# MainController.net
KiCad netlist of a schematic drawn in EAGLE
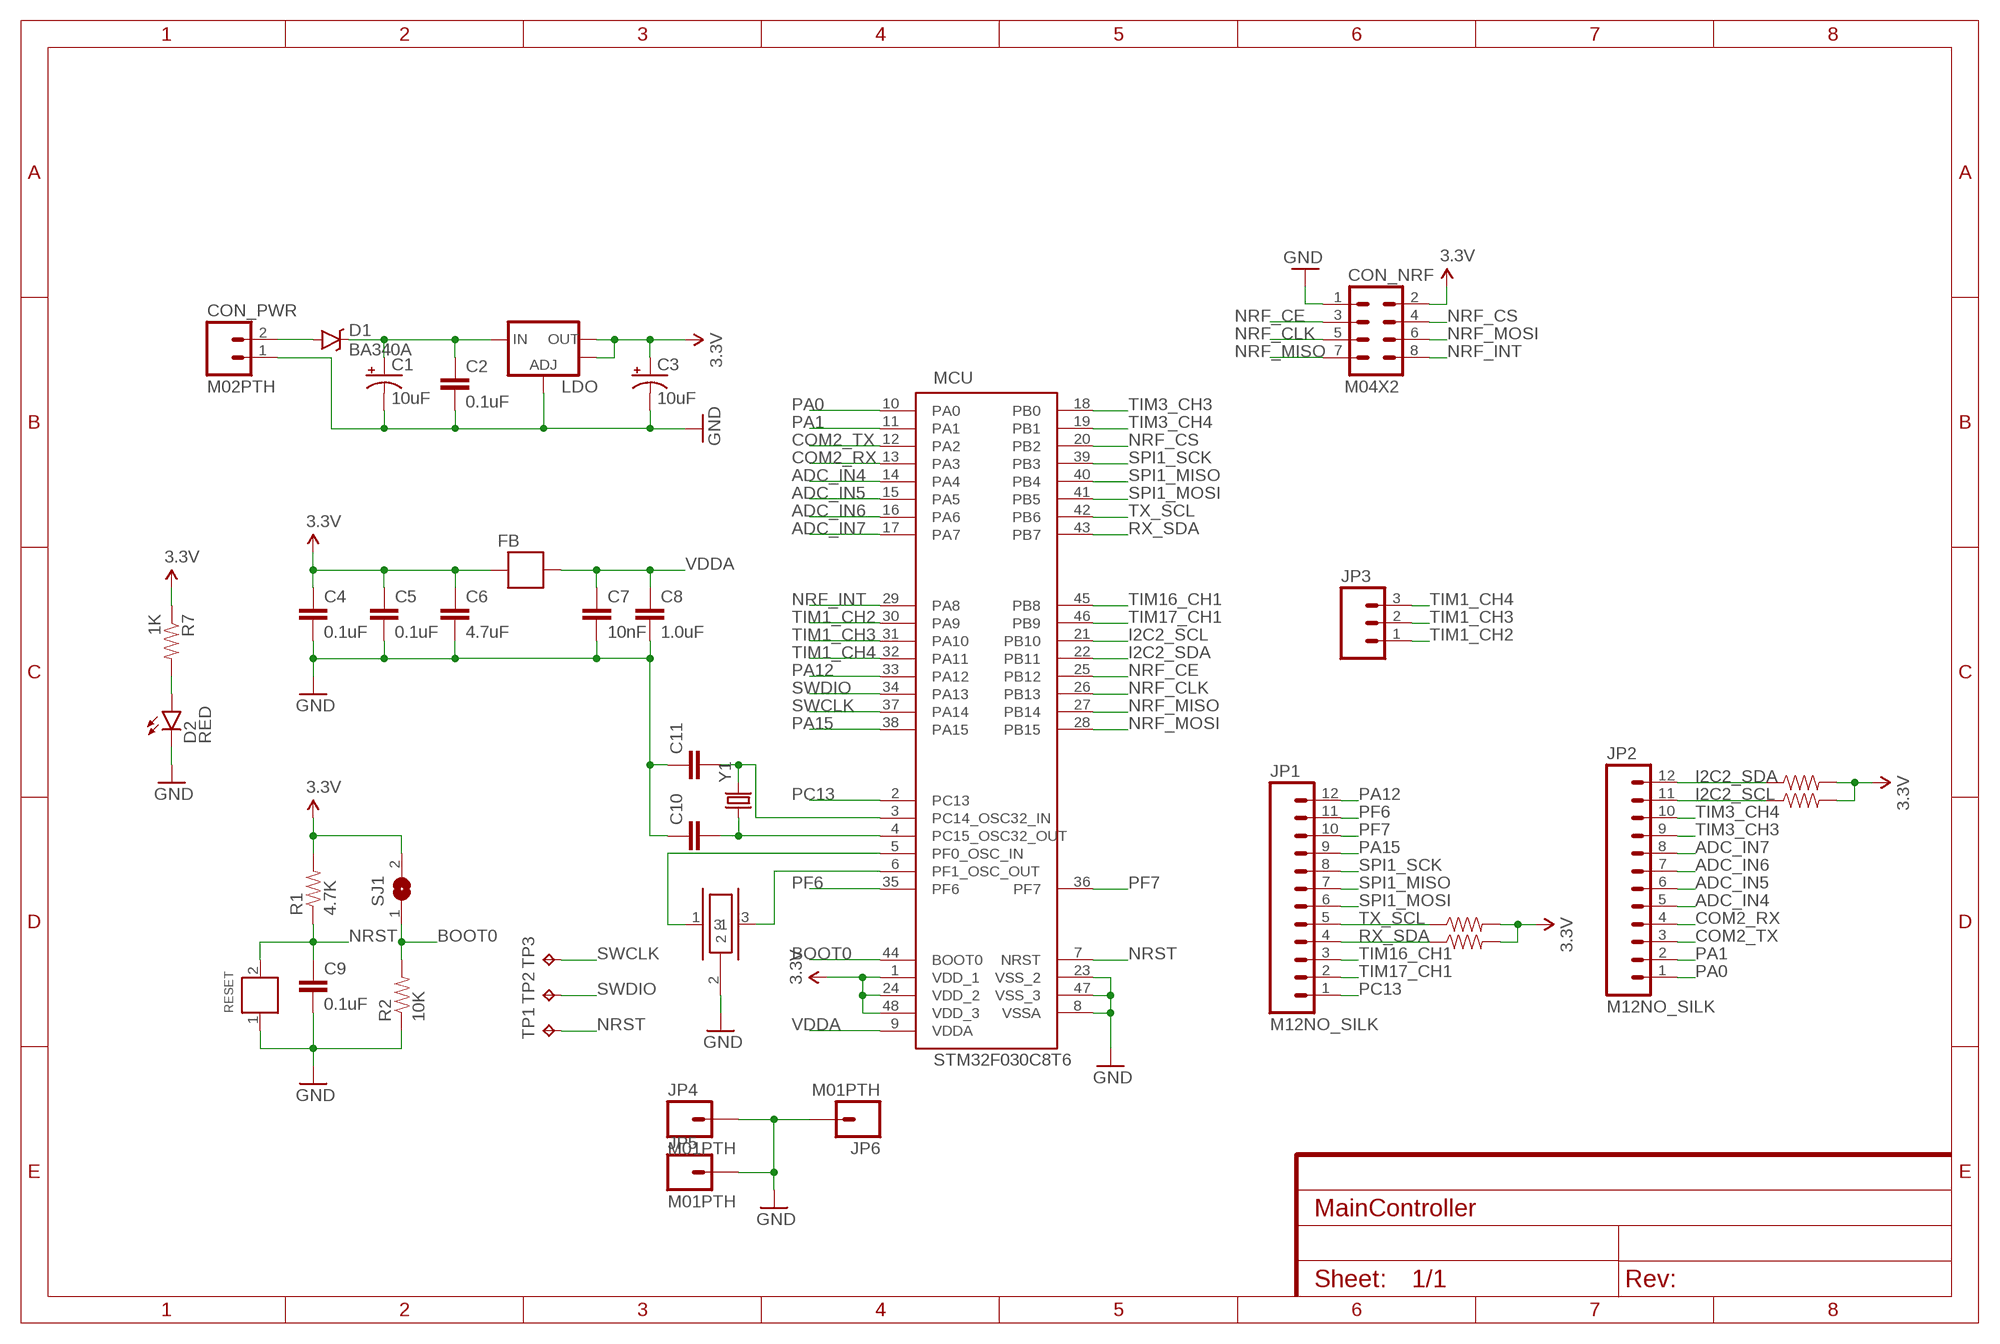
[diagram p0: schematic, sheet 1]

(export (version "E")
  (design (tool "Eeschema 10.0.6"))
  (components
    (comp (ref "C1")
      (value "10uF")
      (footprint "eagle-import:EIA3216")
      (libsource (lib "eagle-import") (part "10UF-16V-10%(TANT)"))
    )
    (comp (ref "C2")
      (value "0.1uF")
      (footprint "eagle-import:0603-CAP")
      (libsource (lib "eagle-import") (part "0.1UF-25V-5%(0603)"))
    )
    (comp (ref "C3")
      (value "10uF")
      (footprint "eagle-import:EIA3216")
      (libsource (lib "eagle-import") (part "10UF-16V-10%(TANT)"))
    )
    (comp (ref "C4")
      (value "0.1uF")
      (footprint "eagle-import:0603-CAP")
      (libsource (lib "eagle-import") (part "0.1UF-25V-5%(0603)"))
    )
    (comp (ref "C5")
      (value "0.1uF")
      (footprint "eagle-import:0603-CAP")
      (libsource (lib "eagle-import") (part "0.1UF-25V-5%(0603)"))
    )
    (comp (ref "C6")
      (value "4.7uF")
      (footprint "eagle-import:0603-CAP")
      (libsource (lib "eagle-import") (part "4.7UF-6.3V-10%(0603)0603"))
    )
    (comp (ref "C7")
      (value "10nF")
      (footprint "eagle-import:0603-CAP")
      (libsource (lib "eagle-import") (part "10NF/10000PF-50V-10%(0603)"))
    )
    (comp (ref "C8")
      (value "1.0uF")
      (footprint "eagle-import:0603-CAP")
      (libsource (lib "eagle-import") (part "1.0UF-16V-10%(0603)"))
    )
    (comp (ref "C9")
      (value "0.1uF")
      (footprint "eagle-import:0603-CAP")
      (libsource (lib "eagle-import") (part "0.1UF-100V-10%(0603)"))
    )
    (comp (ref "C10")
      (value "CAP0603-CAP")
      (footprint "eagle-import:0603-CAP")
      (libsource (lib "eagle-import") (part "CAP0603-CAP"))
    )
    (comp (ref "C11")
      (value "CAP0603-CAP")
      (footprint "eagle-import:0603-CAP")
      (libsource (lib "eagle-import") (part "CAP0603-CAP"))
    )
    (comp (ref "CON_NRF")
      (value "M04X2")
      (footprint "eagle-import:2X4")
      (libsource (lib "eagle-import") (part "M04X2"))
    )
    (comp (ref "CON_PWR")
      (value "M02PTH")
      (footprint "eagle-import:1X02")
      (libsource (lib "eagle-import") (part "M02PTH"))
    )
    (comp (ref "D1")
      (value "BA340A")
      (footprint "eagle-import:SMA-DIODE")
      (libsource (lib "eagle-import") (part "B340A"))
    )
    (comp (ref "D2")
      (value "RED")
      (footprint "eagle-import:LED-0603")
      (libsource (lib "eagle-import") (part "LED-RED0603"))
    )
    (comp (ref "FB")
      (value "FBFB0805")
      (footprint "eagle-import:0805W")
      (libsource (lib "eagle-import") (part "FBFB0805"))
    )
    (comp (ref "JP1")
      (value "M12NO_SILK")
      (footprint "eagle-import:1X12_NO_SILK")
      (libsource (lib "eagle-import") (part "M12NO_SILK"))
    )
    (comp (ref "JP2")
      (value "M12NO_SILK")
      (footprint "eagle-import:1X12_NO_SILK")
      (libsource (lib "eagle-import") (part "M12NO_SILK"))
    )
    (comp (ref "JP3")
      (value "M031X03_NO_SILK")
      (footprint "eagle-import:1X03_NO_SILK")
      (libsource (lib "eagle-import") (part "M031X03_NO_SILK"))
    )
    (comp (ref "JP4")
      (value "M01PTH")
      (footprint "eagle-import:1X01")
      (libsource (lib "eagle-import") (part "M01PTH"))
    )
    (comp (ref "JP5")
      (value "M01PTH")
      (footprint "eagle-import:1X01")
      (libsource (lib "eagle-import") (part "M01PTH"))
    )
    (comp (ref "JP6")
      (value "M01PTH")
      (footprint "eagle-import:1X01")
      (libsource (lib "eagle-import") (part "M01PTH"))
    )
    (comp (ref "LDO")
      (value "V_REG_LM1117SOT223")
      (footprint "eagle-import:SOT223")
      (libsource (lib "eagle-import") (part "V_REG_LM1117SOT223"))
    )
    (comp (ref "MCU")
      (value "STM32F030C8T6")
      (footprint "eagle-import:TQFP48")
      (libsource (lib "eagle-import") (part "STM32F030C8T6"))
    )
    (comp (ref "OSC")
      (value "CSTCE8M00G52-R0")
      (footprint "eagle-import:CSTCE_M_G")
      (libsource (lib "eagle-import") (part "CSTCE8M00G52-R0"))
    )
    (comp (ref "R1")
      (value "4.7K")
      (footprint "eagle-import:0603-RES")
      (libsource (lib "eagle-import") (part "4.7KOHM-1/10W-1%(0603)"))
    )
    (comp (ref "R2")
      (value "10K")
      (footprint "eagle-import:0603-RES")
      (libsource (lib "eagle-import") (part "10KOHM-1/10W-1%(0603)0603"))
    )
    (comp (ref "R3")
      (value "10K")
      (footprint "eagle-import:0603-RES")
      (libsource (lib "eagle-import") (part "10OHM-1/10W-5%0603SMD"))
    )
    (comp (ref "R4")
      (value "10K")
      (footprint "eagle-import:0603-RES")
      (libsource (lib "eagle-import") (part "10OHM-1/10W-5%0603SMD"))
    )
    (comp (ref "R5")
      (value "10K")
      (footprint "eagle-import:0603-RES")
      (libsource (lib "eagle-import") (part "10OHM-1/10W-5%0603SMD"))
    )
    (comp (ref "R6")
      (value "10K")
      (footprint "eagle-import:0603-RES")
      (libsource (lib "eagle-import") (part "10OHM-1/10W-5%0603SMD"))
    )
    (comp (ref "R7")
      (value "1K")
      (footprint "eagle-import:0603-RES")
      (libsource (lib "eagle-import") (part "1KOHM-1/10W-1%(0603)"))
    )
    (comp (ref "RESET")
      (value "SWITCH_SMD")
      (footprint "eagle-import:SWITCH3X6_SMD")
      (libsource (lib "eagle-import") (part "SWITCH_SMD"))
    )
    (comp (ref "SJ1") (value "SJ") (footprint "eagle-import:SJ") (libsource (lib "eagle-import") (part "SJ")))
    (comp (ref "TP1")
      (value "TPB1,27")
      (footprint "eagle-import:B1,27")
      (libsource (lib "eagle-import") (part "TPB1,27"))
    )
    (comp (ref "TP2")
      (value "TPB1,27")
      (footprint "eagle-import:B1,27")
      (libsource (lib "eagle-import") (part "TPB1,27"))
    )
    (comp (ref "TP3")
      (value "TPB1,27")
      (footprint "eagle-import:B1,27")
      (libsource (lib "eagle-import") (part "TPB1,27"))
    )
    (comp (ref "Y1")
      (value "CRYSTALTC38H")
      (footprint "eagle-import:TC38H")
      (libsource (lib "eagle-import") (part "CRYSTALTC38H"))
    )
  )
  (nets
    (net (code "1") (name "/ADC_IN4") (class "Default")
      (node (ref "JP2") (pin "5") (pinfunction "5_5") (pintype "passive"))
      (node (ref "MCU") (pin "14") (pinfunction "PA4_14") (pintype "bidirectional"))
    )
    (net (code "2") (name "/ADC_IN5") (class "Default")
      (node (ref "JP2") (pin "6") (pinfunction "6_6") (pintype "passive"))
      (node (ref "MCU") (pin "15") (pinfunction "PA5_15") (pintype "bidirectional"))
    )
    (net (code "3") (name "/ADC_IN6") (class "Default")
      (node (ref "JP2") (pin "7") (pinfunction "7_7") (pintype "passive"))
      (node (ref "MCU") (pin "16") (pinfunction "PA6_16") (pintype "bidirectional"))
    )
    (net (code "4") (name "/ADC_IN7") (class "Default")
      (node (ref "JP2") (pin "8") (pinfunction "8_8") (pintype "passive"))
      (node (ref "MCU") (pin "17") (pinfunction "PA7_17") (pintype "bidirectional"))
    )
    (net (code "5") (name "/BOOT0") (class "Default")
      (node (ref "MCU") (pin "44") (pinfunction "BOOT0_44") (pintype "bidirectional"))
      (node (ref "R2") (pin "2") (pinfunction "2_2") (pintype "passive"))
      (node (ref "SJ1") (pin "1") (pinfunction "1_1") (pintype "passive"))
    )
    (net (code "6") (name "/COM2_RX") (class "Default")
      (node (ref "JP2") (pin "4") (pinfunction "4_4") (pintype "passive"))
      (node (ref "MCU") (pin "13") (pinfunction "PA3_13") (pintype "bidirectional"))
    )
    (net (code "7") (name "/COM2_TX") (class "Default")
      (node (ref "JP2") (pin "3") (pinfunction "3_3") (pintype "passive"))
      (node (ref "MCU") (pin "12") (pinfunction "PA2_12") (pintype "bidirectional"))
    )
    (net (code "8") (name "/I2C2_SCL") (class "Default")
      (node (ref "JP2") (pin "11") (pinfunction "11_11") (pintype "passive"))
      (node (ref "MCU") (pin "21") (pinfunction "PB10_21") (pintype "bidirectional"))
      (node (ref "R5") (pin "1") (pinfunction "1_1") (pintype "passive"))
    )
    (net (code "9") (name "/I2C2_SDA") (class "Default")
      (node (ref "JP2") (pin "12") (pinfunction "12_12") (pintype "passive"))
      (node (ref "MCU") (pin "22") (pinfunction "PB11_22") (pintype "bidirectional"))
      (node (ref "R6") (pin "1") (pinfunction "1_1") (pintype "passive"))
    )
    (net (code "10") (name "/NRF_CE") (class "Default")
      (node (ref "CON_NRF") (pin "3") (pinfunction "3_3") (pintype "passive"))
      (node (ref "MCU") (pin "25") (pinfunction "PB12_25") (pintype "bidirectional"))
    )
    (net (code "11") (name "/NRF_CLK") (class "Default")
      (node (ref "CON_NRF") (pin "5") (pinfunction "5_5") (pintype "passive"))
      (node (ref "MCU") (pin "26") (pinfunction "PB13_26") (pintype "bidirectional"))
    )
    (net (code "12") (name "/NRF_CS") (class "Default")
      (node (ref "CON_NRF") (pin "4") (pinfunction "4_4") (pintype "passive"))
      (node (ref "MCU") (pin "20") (pinfunction "PB2_20") (pintype "bidirectional"))
    )
    (net (code "13") (name "/NRF_INT") (class "Default")
      (node (ref "CON_NRF") (pin "8") (pinfunction "8_8") (pintype "passive"))
      (node (ref "MCU") (pin "29") (pinfunction "PA8_29") (pintype "bidirectional"))
    )
    (net (code "14") (name "/NRF_MISO") (class "Default")
      (node (ref "CON_NRF") (pin "7") (pinfunction "7_7") (pintype "passive"))
      (node (ref "MCU") (pin "27") (pinfunction "PB14_27") (pintype "bidirectional"))
    )
    (net (code "15") (name "/NRF_MOSI") (class "Default")
      (node (ref "CON_NRF") (pin "6") (pinfunction "6_6") (pintype "passive"))
      (node (ref "MCU") (pin "28") (pinfunction "PB15_28") (pintype "bidirectional"))
    )
    (net (code "16") (name "/NRST") (class "Default")
      (node (ref "C9") (pin "1") (pinfunction "1_1") (pintype "passive"))
      (node (ref "MCU") (pin "7") (pinfunction "NRST_7") (pintype "bidirectional"))
      (node (ref "R1") (pin "1") (pinfunction "1_1") (pintype "passive"))
      (node (ref "RESET") (pin "2") (pinfunction "2_2") (pintype "bidirectional"))
      (node (ref "TP1") (pin "TP") (pinfunction "TP_TP") (pintype "input"))
    )
    (net (code "17") (name "/PA0") (class "Default")
      (node (ref "JP2") (pin "1") (pinfunction "1_1") (pintype "passive"))
      (node (ref "MCU") (pin "10") (pinfunction "PA0_10") (pintype "bidirectional"))
    )
    (net (code "18") (name "/PA1") (class "Default")
      (node (ref "JP2") (pin "2") (pinfunction "2_2") (pintype "passive"))
      (node (ref "MCU") (pin "11") (pinfunction "PA1_11") (pintype "bidirectional"))
    )
    (net (code "19") (name "/PA12") (class "Default")
      (node (ref "JP1") (pin "12") (pinfunction "12_12") (pintype "passive"))
      (node (ref "MCU") (pin "33") (pinfunction "PA12_33") (pintype "bidirectional"))
    )
    (net (code "20") (name "/PA15") (class "Default")
      (node (ref "JP1") (pin "9") (pinfunction "9_9") (pintype "passive"))
      (node (ref "MCU") (pin "38") (pinfunction "PA15_38") (pintype "bidirectional"))
    )
    (net (code "21") (name "/PC13") (class "Default")
      (node (ref "JP1") (pin "1") (pinfunction "1_1") (pintype "passive"))
      (node (ref "MCU") (pin "2") (pinfunction "PC13_2") (pintype "bidirectional"))
    )
    (net (code "22") (name "/PF6") (class "Default")
      (node (ref "JP1") (pin "11") (pinfunction "11_11") (pintype "passive"))
      (node (ref "MCU") (pin "35") (pinfunction "PF6_35") (pintype "bidirectional"))
    )
    (net (code "23") (name "/PF7") (class "Default")
      (node (ref "JP1") (pin "10") (pinfunction "10_10") (pintype "passive"))
      (node (ref "MCU") (pin "36") (pinfunction "PF7_36") (pintype "bidirectional"))
    )
    (net (code "24") (name "/RX_SDA") (class "Default")
      (node (ref "JP1") (pin "4") (pinfunction "4_4") (pintype "passive"))
      (node (ref "MCU") (pin "43") (pinfunction "PB7_43") (pintype "bidirectional"))
      (node (ref "R4") (pin "1") (pinfunction "1_1") (pintype "passive"))
    )
    (net (code "25") (name "/SPI1_MISO") (class "Default")
      (node (ref "JP1") (pin "7") (pinfunction "7_7") (pintype "passive"))
      (node (ref "MCU") (pin "40") (pinfunction "PB4_40") (pintype "bidirectional"))
    )
    (net (code "26") (name "/SPI1_MOSI") (class "Default")
      (node (ref "JP1") (pin "6") (pinfunction "6_6") (pintype "passive"))
      (node (ref "MCU") (pin "41") (pinfunction "PB5_41") (pintype "bidirectional"))
    )
    (net (code "27") (name "/SPI1_SCK") (class "Default")
      (node (ref "JP1") (pin "8") (pinfunction "8_8") (pintype "passive"))
      (node (ref "MCU") (pin "39") (pinfunction "PB3_39") (pintype "bidirectional"))
    )
    (net (code "28") (name "/SWCLK") (class "Default")
      (node (ref "MCU") (pin "37") (pinfunction "PA14_37") (pintype "bidirectional"))
      (node (ref "TP3") (pin "TP") (pinfunction "TP_TP") (pintype "input"))
    )
    (net (code "29") (name "/SWDIO") (class "Default")
      (node (ref "MCU") (pin "34") (pinfunction "PA13_34") (pintype "bidirectional"))
      (node (ref "TP2") (pin "TP") (pinfunction "TP_TP") (pintype "input"))
    )
    (net (code "30") (name "/TIM1_CH2") (class "Default")
      (node (ref "JP3") (pin "1") (pinfunction "1_1") (pintype "passive"))
      (node (ref "MCU") (pin "30") (pinfunction "PA9_30") (pintype "bidirectional"))
    )
    (net (code "31") (name "/TIM1_CH3") (class "Default")
      (node (ref "JP3") (pin "2") (pinfunction "2_2") (pintype "passive"))
      (node (ref "MCU") (pin "31") (pinfunction "PA10_31") (pintype "bidirectional"))
    )
    (net (code "32") (name "/TIM1_CH4") (class "Default")
      (node (ref "JP3") (pin "3") (pinfunction "3_3") (pintype "passive"))
      (node (ref "MCU") (pin "32") (pinfunction "PA11_32") (pintype "bidirectional"))
    )
    (net (code "33") (name "/TIM3_CH3") (class "Default")
      (node (ref "JP2") (pin "9") (pinfunction "9_9") (pintype "passive"))
      (node (ref "MCU") (pin "18") (pinfunction "PB0_18") (pintype "bidirectional"))
    )
    (net (code "34") (name "/TIM3_CH4") (class "Default")
      (node (ref "JP2") (pin "10") (pinfunction "10_10") (pintype "passive"))
      (node (ref "MCU") (pin "19") (pinfunction "PB1_19") (pintype "bidirectional"))
    )
    (net (code "35") (name "/TIM16_CH1") (class "Default")
      (node (ref "JP1") (pin "3") (pinfunction "3_3") (pintype "passive"))
      (node (ref "MCU") (pin "45") (pinfunction "PB8_45") (pintype "bidirectional"))
    )
    (net (code "36") (name "/TIM17_CH1") (class "Default")
      (node (ref "JP1") (pin "2") (pinfunction "2_2") (pintype "passive"))
      (node (ref "MCU") (pin "46") (pinfunction "PB9_46") (pintype "bidirectional"))
    )
    (net (code "37") (name "/TX_SCL") (class "Default")
      (node (ref "JP1") (pin "5") (pinfunction "5_5") (pintype "passive"))
      (node (ref "MCU") (pin "42") (pinfunction "PB6_42") (pintype "bidirectional"))
      (node (ref "R3") (pin "1") (pinfunction "1_1") (pintype "passive"))
    )
    (net (code "38") (name "/VDDA") (class "Default")
      (node (ref "C7") (pin "1") (pinfunction "1_1") (pintype "passive"))
      (node (ref "C8") (pin "1") (pinfunction "1_1") (pintype "passive"))
      (node (ref "FB") (pin "1") (pinfunction "P$1_1") (pintype "bidirectional"))
      (node (ref "MCU") (pin "9") (pinfunction "VDDA_9") (pintype "bidirectional"))
    )
    (net (code "39") (name "3.3V") (class "Default")
      (node (ref "C3") (pin "A") (pinfunction "+_A") (pintype "passive"))
      (node (ref "C4") (pin "1") (pinfunction "1_1") (pintype "passive"))
      (node (ref "C5") (pin "1") (pinfunction "1_1") (pintype "passive"))
      (node (ref "C6") (pin "1") (pinfunction "1_1") (pintype "passive"))
      (node (ref "CON_NRF") (pin "2") (pinfunction "2_2") (pintype "passive"))
      (node (ref "FB") (pin "2") (pinfunction "P$2_2") (pintype "bidirectional"))
      (node (ref "LDO") (pin "2") (pinfunction "OUT_2") (pintype "output"))
      (node (ref "LDO") (pin "4") (pinfunction "OUT_4") (pintype "output"))
      (node (ref "MCU") (pin "1") (pinfunction "VDD_1_1") (pintype "bidirectional"))
      (node (ref "MCU") (pin "24") (pinfunction "VDD_2_24") (pintype "bidirectional"))
      (node (ref "MCU") (pin "48") (pinfunction "VDD_3_48") (pintype "bidirectional"))
      (node (ref "R1") (pin "2") (pinfunction "2_2") (pintype "passive"))
      (node (ref "R3") (pin "2") (pinfunction "2_2") (pintype "passive"))
      (node (ref "R4") (pin "2") (pinfunction "2_2") (pintype "passive"))
      (node (ref "R5") (pin "2") (pinfunction "2_2") (pintype "passive"))
      (node (ref "R6") (pin "2") (pinfunction "2_2") (pintype "passive"))
      (node (ref "R7") (pin "1") (pinfunction "1_1") (pintype "passive"))
      (node (ref "SJ1") (pin "2") (pinfunction "2_2") (pintype "passive"))
    )
    (net (code "40") (name "GND") (class "Default")
      (node (ref "C1") (pin "C") (pinfunction "-_C") (pintype "passive"))
      (node (ref "C10") (pin "1") (pinfunction "1_1") (pintype "passive"))
      (node (ref "C11") (pin "1") (pinfunction "1_1") (pintype "passive"))
      (node (ref "C2") (pin "2") (pinfunction "2_2") (pintype "passive"))
      (node (ref "C3") (pin "C") (pinfunction "-_C") (pintype "passive"))
      (node (ref "C4") (pin "2") (pinfunction "2_2") (pintype "passive"))
      (node (ref "C5") (pin "2") (pinfunction "2_2") (pintype "passive"))
      (node (ref "C6") (pin "2") (pinfunction "2_2") (pintype "passive"))
      (node (ref "C7") (pin "2") (pinfunction "2_2") (pintype "passive"))
      (node (ref "C8") (pin "2") (pinfunction "2_2") (pintype "passive"))
      (node (ref "C9") (pin "2") (pinfunction "2_2") (pintype "passive"))
      (node (ref "CON_NRF") (pin "1") (pinfunction "1_1") (pintype "passive"))
      (node (ref "CON_PWR") (pin "1") (pinfunction "1_1") (pintype "passive"))
      (node (ref "D2") (pin "C") (pinfunction "C_C") (pintype "passive"))
      (node (ref "JP4") (pin "1") (pinfunction "1_1") (pintype "passive"))
      (node (ref "JP5") (pin "1") (pinfunction "1_1") (pintype "passive"))
      (node (ref "JP6") (pin "1") (pinfunction "1_1") (pintype "passive"))
      (node (ref "LDO") (pin "1") (pinfunction "ADJ_1") (pintype "input"))
      (node (ref "MCU") (pin "23") (pinfunction "VSS_2_23") (pintype "bidirectional"))
      (node (ref "MCU") (pin "47") (pinfunction "VSS_3_47") (pintype "bidirectional"))
      (node (ref "MCU") (pin "8") (pinfunction "VSSA_8") (pintype "bidirectional"))
      (node (ref "OSC") (pin "2") (pinfunction "2_2") (pintype "bidirectional"))
      (node (ref "R2") (pin "1") (pinfunction "1_1") (pintype "passive"))
      (node (ref "RESET") (pin "1") (pinfunction "1_1") (pintype "bidirectional"))
    )
    (net (code "41") (name "Net-(C1-+)") (class "Default")
      (node (ref "C1") (pin "A") (pinfunction "+_A") (pintype "passive"))
      (node (ref "C2") (pin "1") (pinfunction "1_1") (pintype "passive"))
      (node (ref "D1") (pin "C") (pinfunction "C_C") (pintype "passive"))
      (node (ref "LDO") (pin "3") (pinfunction "IN_3") (pintype "input"))
    )
    (net (code "42") (name "Net-(CON_PWR-Pad2)") (class "Default")
      (node (ref "CON_PWR") (pin "2") (pinfunction "2_2") (pintype "passive"))
      (node (ref "D1") (pin "A") (pinfunction "A_A") (pintype "passive"))
    )
    (net (code "43") (name "Net-(D2-PadA)") (class "Default")
      (node (ref "D2") (pin "A") (pinfunction "A_A") (pintype "passive"))
      (node (ref "R7") (pin "2") (pinfunction "2_2") (pintype "passive"))
    )
    (net (code "44") (name "Net-(MCU-PC14_OSC32_IN)") (class "Default")
      (node (ref "C11") (pin "2") (pinfunction "2_2") (pintype "passive"))
      (node (ref "MCU") (pin "3") (pinfunction "PC14_OSC32_IN_3") (pintype "bidirectional"))
      (node (ref "Y1") (pin "2") (pinfunction "2_2") (pintype "passive"))
    )
    (net (code "45") (name "Net-(MCU-PC15_OSC32_OUT)") (class "Default")
      (node (ref "C10") (pin "2") (pinfunction "2_2") (pintype "passive"))
      (node (ref "MCU") (pin "4") (pinfunction "PC15_OSC32_OUT_4") (pintype "bidirectional"))
      (node (ref "Y1") (pin "1") (pinfunction "1_1") (pintype "passive"))
    )
    (net (code "46") (name "Net-(MCU-PF0_OSC_IN)") (class "Default")
      (node (ref "MCU") (pin "5") (pinfunction "PF0_OSC_IN_5") (pintype "bidirectional"))
      (node (ref "OSC") (pin "1") (pinfunction "1_1") (pintype "bidirectional"))
    )
    (net (code "47") (name "Net-(MCU-PF1_OSC_OUT)") (class "Default")
      (node (ref "MCU") (pin "6") (pinfunction "PF1_OSC_OUT_6") (pintype "bidirectional"))
      (node (ref "OSC") (pin "3") (pinfunction "3_3") (pintype "bidirectional"))
    )
  )
)
